# BoardB-Connectors.net
KiCad netlist of a schematic drawn in Altium Designer
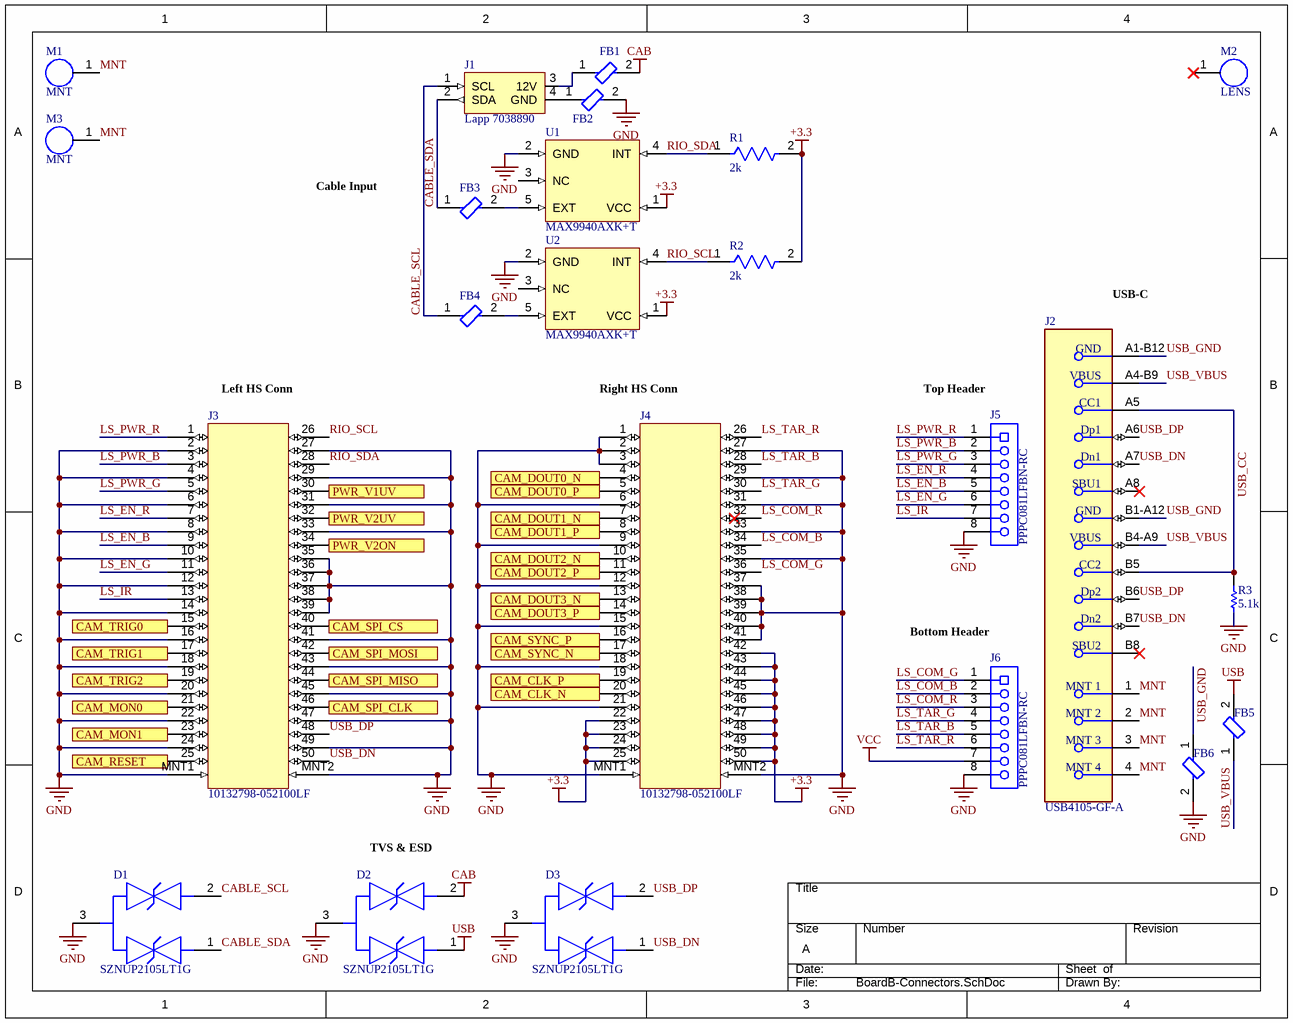
[diagram p0: BoardB-Connectors.SchDoc]

(export (version "E")
  (design (tool "Eeschema 10.0.6"))
  (components
    (comp (ref "D1")
      (value "SZNUP2105LT1G")
      (footprint "FP-318-08-MFG")
      (description "TVS DIODE 24V 44V SOT23-3")
      (fields
        (field (name "OCTOPART") "https://octopart.com/sznup2105lt1g-on+semiconductor-22134626")
        (field (name "MANUFACTURER") "ON Semiconductor")
      )
      (libsource (lib "Altium Content Vault") (part "9fadcfe560bc2ec8fec8016e4fb2740"))
    )
    (comp (ref "D2")
      (value "SZNUP2105LT1G")
      (footprint "FP-318-08-MFG")
      (description "TVS DIODE 24V 44V SOT23-3")
      (fields
        (field (name "OCTOPART") "https://octopart.com/sznup2105lt1g-on+semiconductor-22134626")
        (field (name "MANUFACTURER") "ON Semiconductor")
      )
      (libsource (lib "Altium Content Vault") (part "9fadcfe560bc2ec8fec8016e4fb2740"))
    )
    (comp (ref "D3")
      (value "SZNUP2105LT1G")
      (footprint "FP-318-08-MFG")
      (description "TVS DIODE 24V 44V SOT23-3")
      (fields
        (field (name "OCTOPART") "https://octopart.com/sznup2105lt1g-on+semiconductor-22134626")
        (field (name "MANUFACTURER") "ON Semiconductor")
      )
      (libsource (lib "Altium Content Vault") (part "9fadcfe560bc2ec8fec8016e4fb2740"))
    )
    (comp (ref "FB1")
      (value "BLM18SG221TN1D")
      (footprint "FP-BLM18-0_15-t0_5-IPC_A")
      (description "Chip Ferrite Bead, 0603, 220Ω @ 100MHz, 25%, 0.04Ω, 2.5A")
      (fields (field (name "TOLERANCE") "25%"))
      (libsource (lib "Altium Content Vault") (part "5f30dd21d616792df468990f7003faa"))
    )
    (comp (ref "FB2")
      (value "BLM18SG221TN1D")
      (footprint "FP-BLM18-0_15-t0_5-IPC_A")
      (description "Chip Ferrite Bead, 0603, 220Ω @ 100MHz, 25%, 0.04Ω, 2.5A")
      (fields (field (name "TOLERANCE") "25%"))
      (libsource (lib "Altium Content Vault") (part "5f30dd21d616792df468990f7003faa"))
    )
    (comp (ref "FB3")
      (value "BLM18SG221TN1D")
      (footprint "FP-BLM18-0_15-t0_5-IPC_A")
      (description "Chip Ferrite Bead, 0603, 220Ω @ 100MHz, 25%, 0.04Ω, 2.5A")
      (fields (field (name "TOLERANCE") "25%"))
      (libsource (lib "Altium Content Vault") (part "5f30dd21d616792df468990f7003faa"))
    )
    (comp (ref "FB4")
      (value "BLM18SG221TN1D")
      (footprint "FP-BLM18-0_15-t0_5-IPC_A")
      (description "Chip Ferrite Bead, 0603, 220Ω @ 100MHz, 25%, 0.04Ω, 2.5A")
      (fields (field (name "TOLERANCE") "25%"))
      (libsource (lib "Altium Content Vault") (part "5f30dd21d616792df468990f7003faa"))
    )
    (comp (ref "FB5")
      (value "BLM18SG221TN1D")
      (footprint "FP-BLM18-0_15-t0_5-IPC_A")
      (description "Chip Ferrite Bead, 0603, 220Ω @ 100MHz, 25%, 0.04Ω, 2.5A")
      (fields (field (name "TOLERANCE") "25%"))
      (libsource (lib "Altium Content Vault") (part "5f30dd21d616792df468990f7003faa"))
    )
    (comp (ref "FB6")
      (value "BLM18SG221TN1D")
      (footprint "FP-BLM18-0_15-t0_5-IPC_A")
      (description "Chip Ferrite Bead, 0603, 220Ω @ 100MHz, 25%, 0.04Ω, 2.5A")
      (fields (field (name "TOLERANCE") "25%"))
      (libsource (lib "Altium Content Vault") (part "5f30dd21d616792df468990f7003faa"))
    )
    (comp (ref "J1")
      (value "Lapp 7038890")
      (footprint "Lapp 7038890")
      (libsource (lib "BoardB") (part "Lapp 7038890"))
    )
    (comp (ref "J2")
      (value "USB4105-GF-A")
      (footprint "FP-USB4105-GF-A-MFG")
      (description "CONN RCPT USB2.0 TYPEC 5A")
      (fields
        (field (name "MANUFACTURER") "GCT")
        (field (name "OCTOPART") "https://octopart.com/usb4105-gf-a-gct-106627878")
      )
      (libsource (lib "Altium Content Vault") (part "e7c17a616881a82b79941196b4bec10"))
    )
    (comp (ref "J3")
      (value "10132798-052100LF")
      (footprint "10132798-052100LF")
      (description "50POSITIONING, 2.7MM HEIGHT RECE")
      (libsource (lib "BoardB") (part "10132798-052100LF"))
    )
    (comp (ref "J4")
      (value "10132798-052100LF")
      (footprint "10132798-052100LF")
      (description "50POSITIONING, 2.7MM HEIGHT RECE")
      (libsource (lib "BoardB") (part "10132798-052100LF"))
    )
    (comp (ref "J5")
      (value "PPPC081LFBN-RC")
      (footprint "SLIN-PPPC081LFBN-RC_V")
      (libsource (lib "Altium Content Vault") (part "CN-1P-F-R8"))
    )
    (comp (ref "J6")
      (value "PPPC081LFBN-RC")
      (footprint "SLIN-PPPC081LFBN-RC_V")
      (libsource (lib "Altium Content Vault") (part "CN-1P-F-R8"))
    )
    (comp (ref "M1") (value "MNT") (footprint "MNT") (libsource (lib "BoardB") (part "MNT")))
    (comp (ref "M2") (value "LENS") (footprint "LENS_MNT") (libsource (lib "BoardB") (part "LENS_MNT")))
    (comp (ref "M3") (value "MNT") (footprint "MNT") (libsource (lib "BoardB") (part "MNT")))
    (comp (ref "R1")
      (value "2k")
      (footprint "FP-RC_L0402-MFG")
      (description "RES SMD 2K OHM 1% 1/16W 0402")
      (fields
        (field (name "OCTOPART") "https://octopart.com/rc0402fr-072kl-yageo-5032519")
        (field (name "MANUFACTURER") "Yageo")
      )
      (libsource (lib "Altium Content Vault") (part "1029c3af85768c4190bb7ad29bc67b5"))
    )
    (comp (ref "R2")
      (value "2k")
      (footprint "FP-RC_L0402-MFG")
      (description "RES SMD 2K OHM 1% 1/16W 0402")
      (fields
        (field (name "OCTOPART") "https://octopart.com/rc0402fr-072kl-yageo-5032519")
        (field (name "MANUFACTURER") "Yageo")
      )
      (libsource (lib "Altium Content Vault") (part "1029c3af85768c4190bb7ad29bc67b5"))
    )
    (comp (ref "R3")
      (value "5.1k")
      (footprint "RESC0201(0603)_L")
      (description "5K1 0.05W 5% 0201 (0603 Metric)  SMD")
      (fields (field (name "POWER") "0.05 W") (field (name "TOLERANCE") "5 %"))
      (libsource (lib "Altium Content Vault") (part "RES"))
    )
    (comp (ref "U1")
      (value "MAX9940AXK+T")
      (footprint "MAX9940AXK+T")
      (libsource (lib "BoardB") (part "MAX9940AXK+T"))
    )
    (comp (ref "U2")
      (value "MAX9940AXK+T")
      (footprint "MAX9940AXK+T")
      (libsource (lib "BoardB") (part "MAX9940AXK+T"))
    )
  )
  (nets
    (net (code "1") (name "+3.3") (class "Default")
      (node (ref "J4") (pin "22") (pintype "bidirectional"))
      (node (ref "J4") (pin "23") (pintype "bidirectional"))
      (node (ref "J4") (pin "24") (pintype "bidirectional"))
      (node (ref "J4") (pin "25") (pintype "bidirectional"))
      (node (ref "J4") (pin "42") (pintype "bidirectional"))
      (node (ref "J4") (pin "43") (pintype "bidirectional"))
      (node (ref "J4") (pin "44") (pintype "bidirectional"))
      (node (ref "J4") (pin "45") (pintype "bidirectional"))
      (node (ref "J4") (pin "46") (pintype "bidirectional"))
      (node (ref "J4") (pin "47") (pintype "bidirectional"))
      (node (ref "J4") (pin "48") (pintype "bidirectional"))
      (node (ref "J4") (pin "49") (pintype "bidirectional"))
      (node (ref "J4") (pin "50") (pintype "bidirectional"))
      (node (ref "R1") (pin "2") (pinfunction "2_2") (pintype "passive"))
      (node (ref "R2") (pin "2") (pinfunction "2_2") (pintype "passive"))
      (node (ref "U1") (pin "1") (pinfunction "VCC_1") (pintype "input"))
      (node (ref "U2") (pin "1") (pinfunction "VCC_1") (pintype "input"))
    )
    (net (code "2") (name "/CABLE_SCL") (class "Default")
      (node (ref "D1") (pin "2") (pinfunction "2_2") (pintype "passive"))
      (node (ref "FB4") (pin "1") (pinfunction "1_1") (pintype "passive"))
      (node (ref "J1") (pin "1") (pinfunction "SCL_1") (pintype "input"))
    )
    (net (code "3") (name "/CABLE_SDA") (class "Default")
      (node (ref "D1") (pin "1") (pinfunction "1_1") (pintype "passive"))
      (node (ref "FB3") (pin "1") (pinfunction "1_1") (pintype "passive"))
      (node (ref "J1") (pin "2") (pinfunction "SDA_2") (pintype "output"))
    )
    (net (code "4") (name "/CAM_CLK_N") (class "Default")
      (node (ref "J4") (pin "20") (pintype "bidirectional"))
    )
    (net (code "5") (name "/CAM_CLK_P") (class "Default")
      (node (ref "J4") (pin "19") (pintype "bidirectional"))
    )
    (net (code "6") (name "/CAM_DOUT0_N") (class "Default")
      (node (ref "J4") (pin "4") (pintype "bidirectional"))
    )
    (net (code "7") (name "/CAM_DOUT0_P") (class "Default")
      (node (ref "J4") (pin "5") (pintype "bidirectional"))
    )
    (net (code "8") (name "/CAM_DOUT1_N") (class "Default")
      (node (ref "J4") (pin "7") (pintype "bidirectional"))
    )
    (net (code "9") (name "/CAM_DOUT1_P") (class "Default")
      (node (ref "J4") (pin "8") (pintype "bidirectional"))
    )
    (net (code "10") (name "/CAM_DOUT2_N") (class "Default")
      (node (ref "J4") (pin "10") (pintype "bidirectional"))
    )
    (net (code "11") (name "/CAM_DOUT2_P") (class "Default")
      (node (ref "J4") (pin "11") (pintype "bidirectional"))
    )
    (net (code "12") (name "/CAM_DOUT3_N") (class "Default")
      (node (ref "J4") (pin "13") (pintype "bidirectional"))
    )
    (net (code "13") (name "/CAM_DOUT3_P") (class "Default")
      (node (ref "J4") (pin "14") (pintype "bidirectional"))
    )
    (net (code "14") (name "/CAM_MON0") (class "Default")
      (node (ref "J3") (pin "21") (pintype "bidirectional"))
    )
    (net (code "15") (name "/CAM_MON1") (class "Default")
      (node (ref "J3") (pin "23") (pintype "bidirectional"))
    )
    (net (code "16") (name "/CAM_RESET") (class "Default")
      (node (ref "J3") (pin "25") (pintype "bidirectional"))
    )
    (net (code "17") (name "/CAM_SPI_CLK") (class "Default")
      (node (ref "J3") (pin "46") (pintype "bidirectional"))
    )
    (net (code "18") (name "/CAM_SPI_CS") (class "Default")
      (node (ref "J3") (pin "40") (pintype "bidirectional"))
    )
    (net (code "19") (name "/CAM_SPI_MISO") (class "Default")
      (node (ref "J3") (pin "44") (pintype "bidirectional"))
    )
    (net (code "20") (name "/CAM_SPI_MOSI") (class "Default")
      (node (ref "J3") (pin "42") (pintype "bidirectional"))
    )
    (net (code "21") (name "/CAM_SYNC_N") (class "Default")
      (node (ref "J4") (pin "17") (pintype "bidirectional"))
    )
    (net (code "22") (name "/CAM_SYNC_P") (class "Default")
      (node (ref "J4") (pin "16") (pintype "bidirectional"))
    )
    (net (code "23") (name "/CAM_TRIG0") (class "Default")
      (node (ref "J3") (pin "15") (pintype "bidirectional"))
    )
    (net (code "24") (name "/CAM_TRIG1") (class "Default")
      (node (ref "J3") (pin "17") (pintype "bidirectional"))
    )
    (net (code "25") (name "/CAM_TRIG2") (class "Default")
      (node (ref "J3") (pin "19") (pintype "bidirectional"))
    )
    (net (code "26") (name "/LS_COM_B") (class "Default")
      (node (ref "J4") (pin "34") (pintype "bidirectional"))
      (node (ref "J6") (pin "2") (pinfunction "2_2") (pintype "passive"))
    )
    (net (code "27") (name "/LS_COM_G") (class "Default")
      (node (ref "J4") (pin "36") (pintype "bidirectional"))
      (node (ref "J6") (pin "1") (pinfunction "1_1") (pintype "passive"))
    )
    (net (code "28") (name "/LS_COM_R") (class "Default")
      (node (ref "J4") (pin "32") (pintype "bidirectional"))
      (node (ref "J6") (pin "3") (pinfunction "3_3") (pintype "passive"))
    )
    (net (code "29") (name "/LS_EN_B") (class "Default")
      (node (ref "J3") (pin "9") (pintype "bidirectional"))
      (node (ref "J5") (pin "5") (pinfunction "5_5") (pintype "passive"))
    )
    (net (code "30") (name "/LS_EN_G") (class "Default")
      (node (ref "J3") (pin "11") (pintype "bidirectional"))
      (node (ref "J5") (pin "6") (pinfunction "6_6") (pintype "passive"))
    )
    (net (code "31") (name "/LS_EN_R") (class "Default")
      (node (ref "J3") (pin "7") (pintype "bidirectional"))
      (node (ref "J5") (pin "4") (pinfunction "4_4") (pintype "passive"))
    )
    (net (code "32") (name "/LS_IR") (class "Default")
      (node (ref "J3") (pin "13") (pintype "bidirectional"))
      (node (ref "J5") (pin "7") (pinfunction "7_7") (pintype "passive"))
    )
    (net (code "33") (name "/LS_PWR_B") (class "Default")
      (node (ref "J3") (pin "3") (pintype "bidirectional"))
      (node (ref "J5") (pin "2") (pinfunction "2_2") (pintype "passive"))
    )
    (net (code "34") (name "/LS_PWR_G") (class "Default")
      (node (ref "J3") (pin "5") (pintype "bidirectional"))
      (node (ref "J5") (pin "3") (pinfunction "3_3") (pintype "passive"))
    )
    (net (code "35") (name "/LS_PWR_R") (class "Default")
      (node (ref "J3") (pin "1") (pintype "bidirectional"))
      (node (ref "J5") (pin "1") (pinfunction "1_1") (pintype "passive"))
    )
    (net (code "36") (name "/LS_TAR_B") (class "Default")
      (node (ref "J4") (pin "28") (pintype "bidirectional"))
      (node (ref "J6") (pin "5") (pinfunction "5_5") (pintype "passive"))
    )
    (net (code "37") (name "/LS_TAR_G") (class "Default")
      (node (ref "J4") (pin "30") (pintype "bidirectional"))
      (node (ref "J6") (pin "4") (pinfunction "4_4") (pintype "passive"))
    )
    (net (code "38") (name "/LS_TAR_R") (class "Default")
      (node (ref "J4") (pin "26") (pintype "bidirectional"))
      (node (ref "J6") (pin "6") (pinfunction "6_6") (pintype "passive"))
    )
    (net (code "39") (name "/MNT") (class "Default")
      (node (ref "J2") (pin "1") (pinfunction "MNT_1_1") (pintype "power_in"))
      (node (ref "J2") (pin "2") (pinfunction "MNT_2_2") (pintype "power_in"))
      (node (ref "J2") (pin "3") (pinfunction "MNT_3_3") (pintype "power_in"))
      (node (ref "J2") (pin "4") (pinfunction "MNT_4_4") (pintype "power_in"))
      (node (ref "M1") (pin "1") (pintype "passive"))
      (node (ref "M3") (pin "1") (pintype "passive"))
    )
    (net (code "40") (name "/PWR_V1UV") (class "Default")
      (node (ref "J3") (pin "30") (pintype "bidirectional"))
    )
    (net (code "41") (name "/PWR_V2ON") (class "Default")
      (node (ref "J3") (pin "34") (pintype "bidirectional"))
    )
    (net (code "42") (name "/PWR_V2UV") (class "Default")
      (node (ref "J3") (pin "32") (pintype "bidirectional"))
    )
    (net (code "43") (name "/RIO_SCL") (class "Default")
      (node (ref "J3") (pin "26") (pintype "bidirectional"))
      (node (ref "R2") (pin "1") (pinfunction "1_1") (pintype "passive"))
      (node (ref "U2") (pin "4") (pinfunction "INT_4") (pintype "input"))
    )
    (net (code "44") (name "/RIO_SDA") (class "Default")
      (node (ref "J3") (pin "28") (pintype "bidirectional"))
      (node (ref "R1") (pin "1") (pinfunction "1_1") (pintype "passive"))
      (node (ref "U1") (pin "4") (pinfunction "INT_4") (pintype "input"))
    )
    (net (code "45") (name "/USB_CC") (class "Default")
      (node (ref "J2") (pin "A5") (pinfunction "CC1_A5") (pintype "power_in"))
      (node (ref "J2") (pin "B5") (pinfunction "CC2_B5") (pintype "bidirectional"))
      (node (ref "R3") (pin "2") (pinfunction "2_2") (pintype "passive"))
    )
    (net (code "46") (name "/USB_DN") (class "Default")
      (node (ref "D3") (pin "1") (pinfunction "1_1") (pintype "passive"))
      (node (ref "J2") (pin "A7") (pinfunction "Dn1_A7") (pintype "bidirectional"))
      (node (ref "J2") (pin "B7") (pinfunction "Dn2_B7") (pintype "bidirectional"))
      (node (ref "J3") (pin "50") (pintype "bidirectional"))
    )
    (net (code "47") (name "/USB_DP") (class "Default")
      (node (ref "D3") (pin "2") (pinfunction "2_2") (pintype "passive"))
      (node (ref "J2") (pin "A6") (pinfunction "Dp1_A6") (pintype "bidirectional"))
      (node (ref "J2") (pin "B6") (pinfunction "Dp2_B6") (pintype "bidirectional"))
      (node (ref "J3") (pin "48") (pintype "bidirectional"))
    )
    (net (code "48") (name "/USB_GND") (class "Default")
      (node (ref "FB6") (pin "1") (pinfunction "1_1") (pintype "passive"))
      (node (ref "J2") (pin "A1-B12") (pinfunction "GND_A1-B12") (pintype "power_in"))
      (node (ref "J2") (pin "B1-A12") (pinfunction "GND_B1-A12") (pintype "bidirectional"))
    )
    (net (code "49") (name "/USB_VBUS") (class "Default")
      (node (ref "FB5") (pin "1") (pinfunction "1_1") (pintype "passive"))
      (node (ref "J2") (pin "A4-B9") (pinfunction "VBUS_A4-B9") (pintype "power_in"))
      (node (ref "J2") (pin "B4-A9") (pinfunction "VBUS_B4-A9") (pintype "bidirectional"))
    )
    (net (code "50") (name "CAB") (class "Default")
      (node (ref "D2") (pin "2") (pinfunction "2_2") (pintype "passive"))
      (node (ref "FB1") (pin "2") (pinfunction "2_2") (pintype "passive"))
    )
    (net (code "51") (name "GND") (class "Default")
      (node (ref "D1") (pin "3") (pinfunction "3_3") (pintype "passive"))
      (node (ref "D2") (pin "3") (pinfunction "3_3") (pintype "passive"))
      (node (ref "D3") (pin "3") (pinfunction "3_3") (pintype "passive"))
      (node (ref "FB2") (pin "2") (pinfunction "2_2") (pintype "passive"))
      (node (ref "FB6") (pin "2") (pinfunction "2_2") (pintype "passive"))
      (node (ref "J3") (pin "10") (pintype "bidirectional"))
      (node (ref "J3") (pin "12") (pintype "bidirectional"))
      (node (ref "J3") (pin "14") (pintype "bidirectional"))
      (node (ref "J3") (pin "16") (pintype "bidirectional"))
      (node (ref "J3") (pin "18") (pintype "bidirectional"))
      (node (ref "J3") (pin "2") (pintype "bidirectional"))
      (node (ref "J3") (pin "20") (pintype "bidirectional"))
      (node (ref "J3") (pin "22") (pintype "bidirectional"))
      (node (ref "J3") (pin "24") (pintype "bidirectional"))
      (node (ref "J3") (pin "27") (pintype "bidirectional"))
      (node (ref "J3") (pin "29") (pintype "bidirectional"))
      (node (ref "J3") (pin "31") (pintype "bidirectional"))
      (node (ref "J3") (pin "33") (pintype "bidirectional"))
      (node (ref "J3") (pin "35") (pintype "bidirectional"))
      (node (ref "J3") (pin "36") (pintype "bidirectional"))
      (node (ref "J3") (pin "37") (pintype "bidirectional"))
      (node (ref "J3") (pin "38") (pintype "bidirectional"))
      (node (ref "J3") (pin "39") (pintype "bidirectional"))
      (node (ref "J3") (pin "4") (pintype "bidirectional"))
      (node (ref "J3") (pin "41") (pintype "bidirectional"))
      (node (ref "J3") (pin "43") (pintype "bidirectional"))
      (node (ref "J3") (pin "45") (pintype "bidirectional"))
      (node (ref "J3") (pin "47") (pintype "bidirectional"))
      (node (ref "J3") (pin "49") (pintype "bidirectional"))
      (node (ref "J3") (pin "6") (pintype "bidirectional"))
      (node (ref "J3") (pin "8") (pintype "bidirectional"))
      (node (ref "J3") (pin "MNT1") (pintype "input"))
      (node (ref "J3") (pin "MNT2") (pintype "input"))
      (node (ref "J4") (pin "1") (pintype "bidirectional"))
      (node (ref "J4") (pin "12") (pintype "bidirectional"))
      (node (ref "J4") (pin "15") (pintype "bidirectional"))
      (node (ref "J4") (pin "18") (pintype "bidirectional"))
      (node (ref "J4") (pin "2") (pintype "bidirectional"))
      (node (ref "J4") (pin "21") (pintype "bidirectional"))
      (node (ref "J4") (pin "27") (pintype "bidirectional"))
      (node (ref "J4") (pin "29") (pintype "bidirectional"))
      (node (ref "J4") (pin "3") (pintype "bidirectional"))
      (node (ref "J4") (pin "31") (pintype "bidirectional"))
      (node (ref "J4") (pin "33") (pintype "bidirectional"))
      (node (ref "J4") (pin "35") (pintype "bidirectional"))
      (node (ref "J4") (pin "37") (pintype "bidirectional"))
      (node (ref "J4") (pin "38") (pintype "bidirectional"))
      (node (ref "J4") (pin "39") (pintype "bidirectional"))
      (node (ref "J4") (pin "40") (pintype "bidirectional"))
      (node (ref "J4") (pin "41") (pintype "bidirectional"))
      (node (ref "J4") (pin "6") (pintype "bidirectional"))
      (node (ref "J4") (pin "9") (pintype "bidirectional"))
      (node (ref "J4") (pin "MNT1") (pintype "input"))
      (node (ref "J4") (pin "MNT2") (pintype "input"))
      (node (ref "J5") (pin "8") (pinfunction "8_8") (pintype "passive"))
      (node (ref "J6") (pin "8") (pinfunction "8_8") (pintype "passive"))
      (node (ref "R3") (pin "1") (pinfunction "1_1") (pintype "passive"))
      (node (ref "U1") (pin "2") (pinfunction "GND_2") (pintype "input"))
      (node (ref "U2") (pin "2") (pinfunction "GND_2") (pintype "input"))
    )
    (net (code "52") (name "Net-(J1-12V)") (class "Default")
      (node (ref "FB1") (pin "1") (pinfunction "1_1") (pintype "passive"))
      (node (ref "J1") (pin "3") (pinfunction "12V_3") (pintype "power_in"))
    )
    (net (code "53") (name "Net-(J1-GND)") (class "Default")
      (node (ref "FB2") (pin "1") (pinfunction "1_1") (pintype "passive"))
      (node (ref "J1") (pin "4") (pinfunction "GND_4") (pintype "power_in"))
    )
    (net (code "54") (name "Net-(U1-EXT)") (class "Default")
      (node (ref "FB3") (pin "2") (pinfunction "2_2") (pintype "passive"))
      (node (ref "U1") (pin "5") (pinfunction "EXT_5") (pintype "input"))
    )
    (net (code "55") (name "Net-(U2-EXT)") (class "Default")
      (node (ref "FB4") (pin "2") (pinfunction "2_2") (pintype "passive"))
      (node (ref "U2") (pin "5") (pinfunction "EXT_5") (pintype "input"))
    )
    (net (code "56") (name "USB") (class "Default")
      (node (ref "D2") (pin "1") (pinfunction "1_1") (pintype "passive"))
      (node (ref "FB5") (pin "2") (pinfunction "2_2") (pintype "passive"))
    )
    (net (code "57") (name "VCC") (class "Default")
      (node (ref "J6") (pin "7") (pinfunction "7_7") (pintype "passive"))
    )
    (net (code "58") (name "unconnected-(J2-SBU1-PadA8)") (class "Default")
      (node (ref "J2") (pin "A8") (pinfunction "SBU1_A8") (pintype "bidirectional+no_connect"))
    )
    (net (code "59") (name "unconnected-(J2-SBU2-PadB8)") (class "Default")
      (node (ref "J2") (pin "B8") (pinfunction "SBU2_B8") (pintype "power_in+no_connect"))
    )
    (net (code "60") (name "unconnected-(M2-Pad1)") (class "Default")
      (node (ref "M2") (pin "1") (pintype "passive+no_connect"))
    )
    (net (code "61") (name "unconnected-(U1-NC-Pad3)") (class "Default")
      (node (ref "U1") (pin "3") (pinfunction "NC_3") (pintype "input"))
    )
    (net (code "62") (name "unconnected-(U2-NC-Pad3)") (class "Default")
      (node (ref "U2") (pin "3") (pinfunction "NC_3") (pintype "input"))
    )
  )
)
